# levelshift6x.net
KiCad netlist of a schematic drawn in Altium Designer
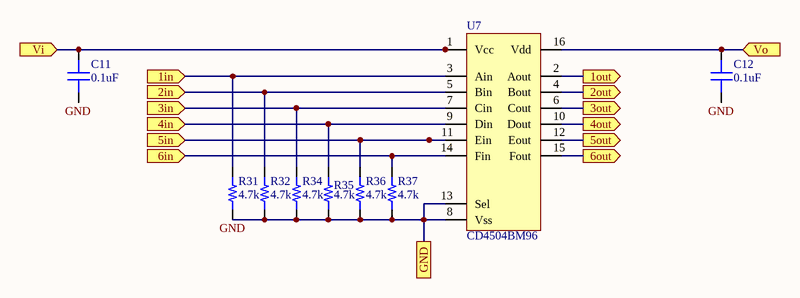
[diagram p0: levelshift6x.SchDoc]

(export (version "E")
  (design (tool "Eeschema 10.0.6"))
  (components
    (comp (ref "C11")
      (value "capacitor")
      (footprint "0603")
      (description "Generic 0603 capacitor")
      (fields (field (name "CAPACITANCE") "0.1uF"))
      (libsource (lib "altlib") (part "capacitor"))
    )
    (comp (ref "C12")
      (value "capacitor")
      (footprint "0603")
      (description "Generic 0603 capacitor")
      (fields (field (name "CAPACITANCE") "0.1uF"))
      (libsource (lib "altlib") (part "capacitor"))
    )
    (comp (ref "R31")
      (value "resistor")
      (footprint "0603")
      (fields (field (name "RESISTANCE") "4.7k"))
      (libsource (lib "altlib") (part "resistor"))
    )
    (comp (ref "R32")
      (value "resistor")
      (footprint "0603")
      (fields (field (name "RESISTANCE") "4.7k"))
      (libsource (lib "altlib") (part "resistor"))
    )
    (comp (ref "R34")
      (value "resistor")
      (footprint "0603")
      (fields (field (name "RESISTANCE") "4.7k"))
      (libsource (lib "altlib") (part "resistor"))
    )
    (comp (ref "R35")
      (value "resistor")
      (footprint "0603")
      (fields (field (name "RESISTANCE") "4.7k"))
      (libsource (lib "altlib") (part "resistor"))
    )
    (comp (ref "R36")
      (value "resistor")
      (footprint "0603")
      (fields (field (name "RESISTANCE") "4.7k"))
      (libsource (lib "altlib") (part "resistor"))
    )
    (comp (ref "R37")
      (value "resistor")
      (footprint "0603")
      (fields (field (name "RESISTANCE") "4.7k"))
      (libsource (lib "altlib") (part "resistor"))
    )
    (comp (ref "U7")
      (value "CD4504BM96")
      (footprint "SOIC-16")
      (description "Voltage Level Translator Unidirectional 1 Cir")
      (libsource (lib "altlib") (part "CD4504BM96"))
    )
  )
  (nets
    (net (code "1") (name "/1in") (class "Default")
      (node (ref "R31") (pin "2") (pinfunction "2_2") (pintype "passive"))
      (node (ref "U7") (pin "3") (pinfunction "Ain_3") (pintype "passive"))
    )
    (net (code "2") (name "/1out") (class "Default")
      (node (ref "U7") (pin "2") (pinfunction "Aout_2") (pintype "passive"))
    )
    (net (code "3") (name "/2in") (class "Default")
      (node (ref "R32") (pin "2") (pinfunction "2_2") (pintype "passive"))
      (node (ref "U7") (pin "5") (pinfunction "Bin_5") (pintype "passive"))
    )
    (net (code "4") (name "/2out") (class "Default")
      (node (ref "U7") (pin "4") (pinfunction "Bout_4") (pintype "passive"))
    )
    (net (code "5") (name "/3in") (class "Default")
      (node (ref "R34") (pin "2") (pinfunction "2_2") (pintype "passive"))
      (node (ref "U7") (pin "7") (pinfunction "Cin_7") (pintype "passive"))
    )
    (net (code "6") (name "/3out") (class "Default")
      (node (ref "U7") (pin "6") (pinfunction "Cout_6") (pintype "passive"))
    )
    (net (code "7") (name "/4in") (class "Default")
      (node (ref "R35") (pin "2") (pinfunction "2_2") (pintype "passive"))
      (node (ref "U7") (pin "9") (pinfunction "Din_9") (pintype "passive"))
    )
    (net (code "8") (name "/4out") (class "Default")
      (node (ref "U7") (pin "10") (pinfunction "Dout_10") (pintype "passive"))
    )
    (net (code "9") (name "/5in") (class "Default")
      (node (ref "R36") (pin "2") (pinfunction "2_2") (pintype "passive"))
      (node (ref "U7") (pin "11") (pinfunction "Ein_11") (pintype "passive"))
    )
    (net (code "10") (name "/5out") (class "Default")
      (node (ref "U7") (pin "12") (pinfunction "Eout_12") (pintype "passive"))
    )
    (net (code "11") (name "/6in") (class "Default")
      (node (ref "R37") (pin "2") (pinfunction "2_2") (pintype "passive"))
      (node (ref "U7") (pin "14") (pinfunction "Fin_14") (pintype "passive"))
    )
    (net (code "12") (name "/6out") (class "Default")
      (node (ref "U7") (pin "15") (pinfunction "Fout_15") (pintype "passive"))
    )
    (net (code "13") (name "/GND") (class "Default")
      (node (ref "C11") (pin "1") (pinfunction "1_1") (pintype "passive"))
      (node (ref "C12") (pin "1") (pinfunction "1_1") (pintype "passive"))
      (node (ref "R31") (pin "1") (pinfunction "1_1") (pintype "passive"))
      (node (ref "R32") (pin "1") (pinfunction "1_1") (pintype "passive"))
      (node (ref "R34") (pin "1") (pinfunction "1_1") (pintype "passive"))
      (node (ref "R35") (pin "1") (pinfunction "1_1") (pintype "passive"))
      (node (ref "R36") (pin "1") (pinfunction "1_1") (pintype "passive"))
      (node (ref "R37") (pin "1") (pinfunction "1_1") (pintype "passive"))
      (node (ref "U7") (pin "13") (pinfunction "Sel_13") (pintype "passive"))
      (node (ref "U7") (pin "8") (pinfunction "Vss_8") (pintype "passive"))
    )
    (net (code "14") (name "/Vi") (class "Default")
      (node (ref "C11") (pin "2") (pinfunction "2_2") (pintype "passive"))
      (node (ref "U7") (pin "1") (pinfunction "Vcc_1") (pintype "passive"))
    )
    (net (code "15") (name "/Vo") (class "Default")
      (node (ref "C12") (pin "2") (pinfunction "2_2") (pintype "passive"))
      (node (ref "U7") (pin "16") (pinfunction "Vdd_16") (pintype "passive"))
    )
  )
)
